# Tah.net
KiCad netlist of a schematic drawn in EAGLE
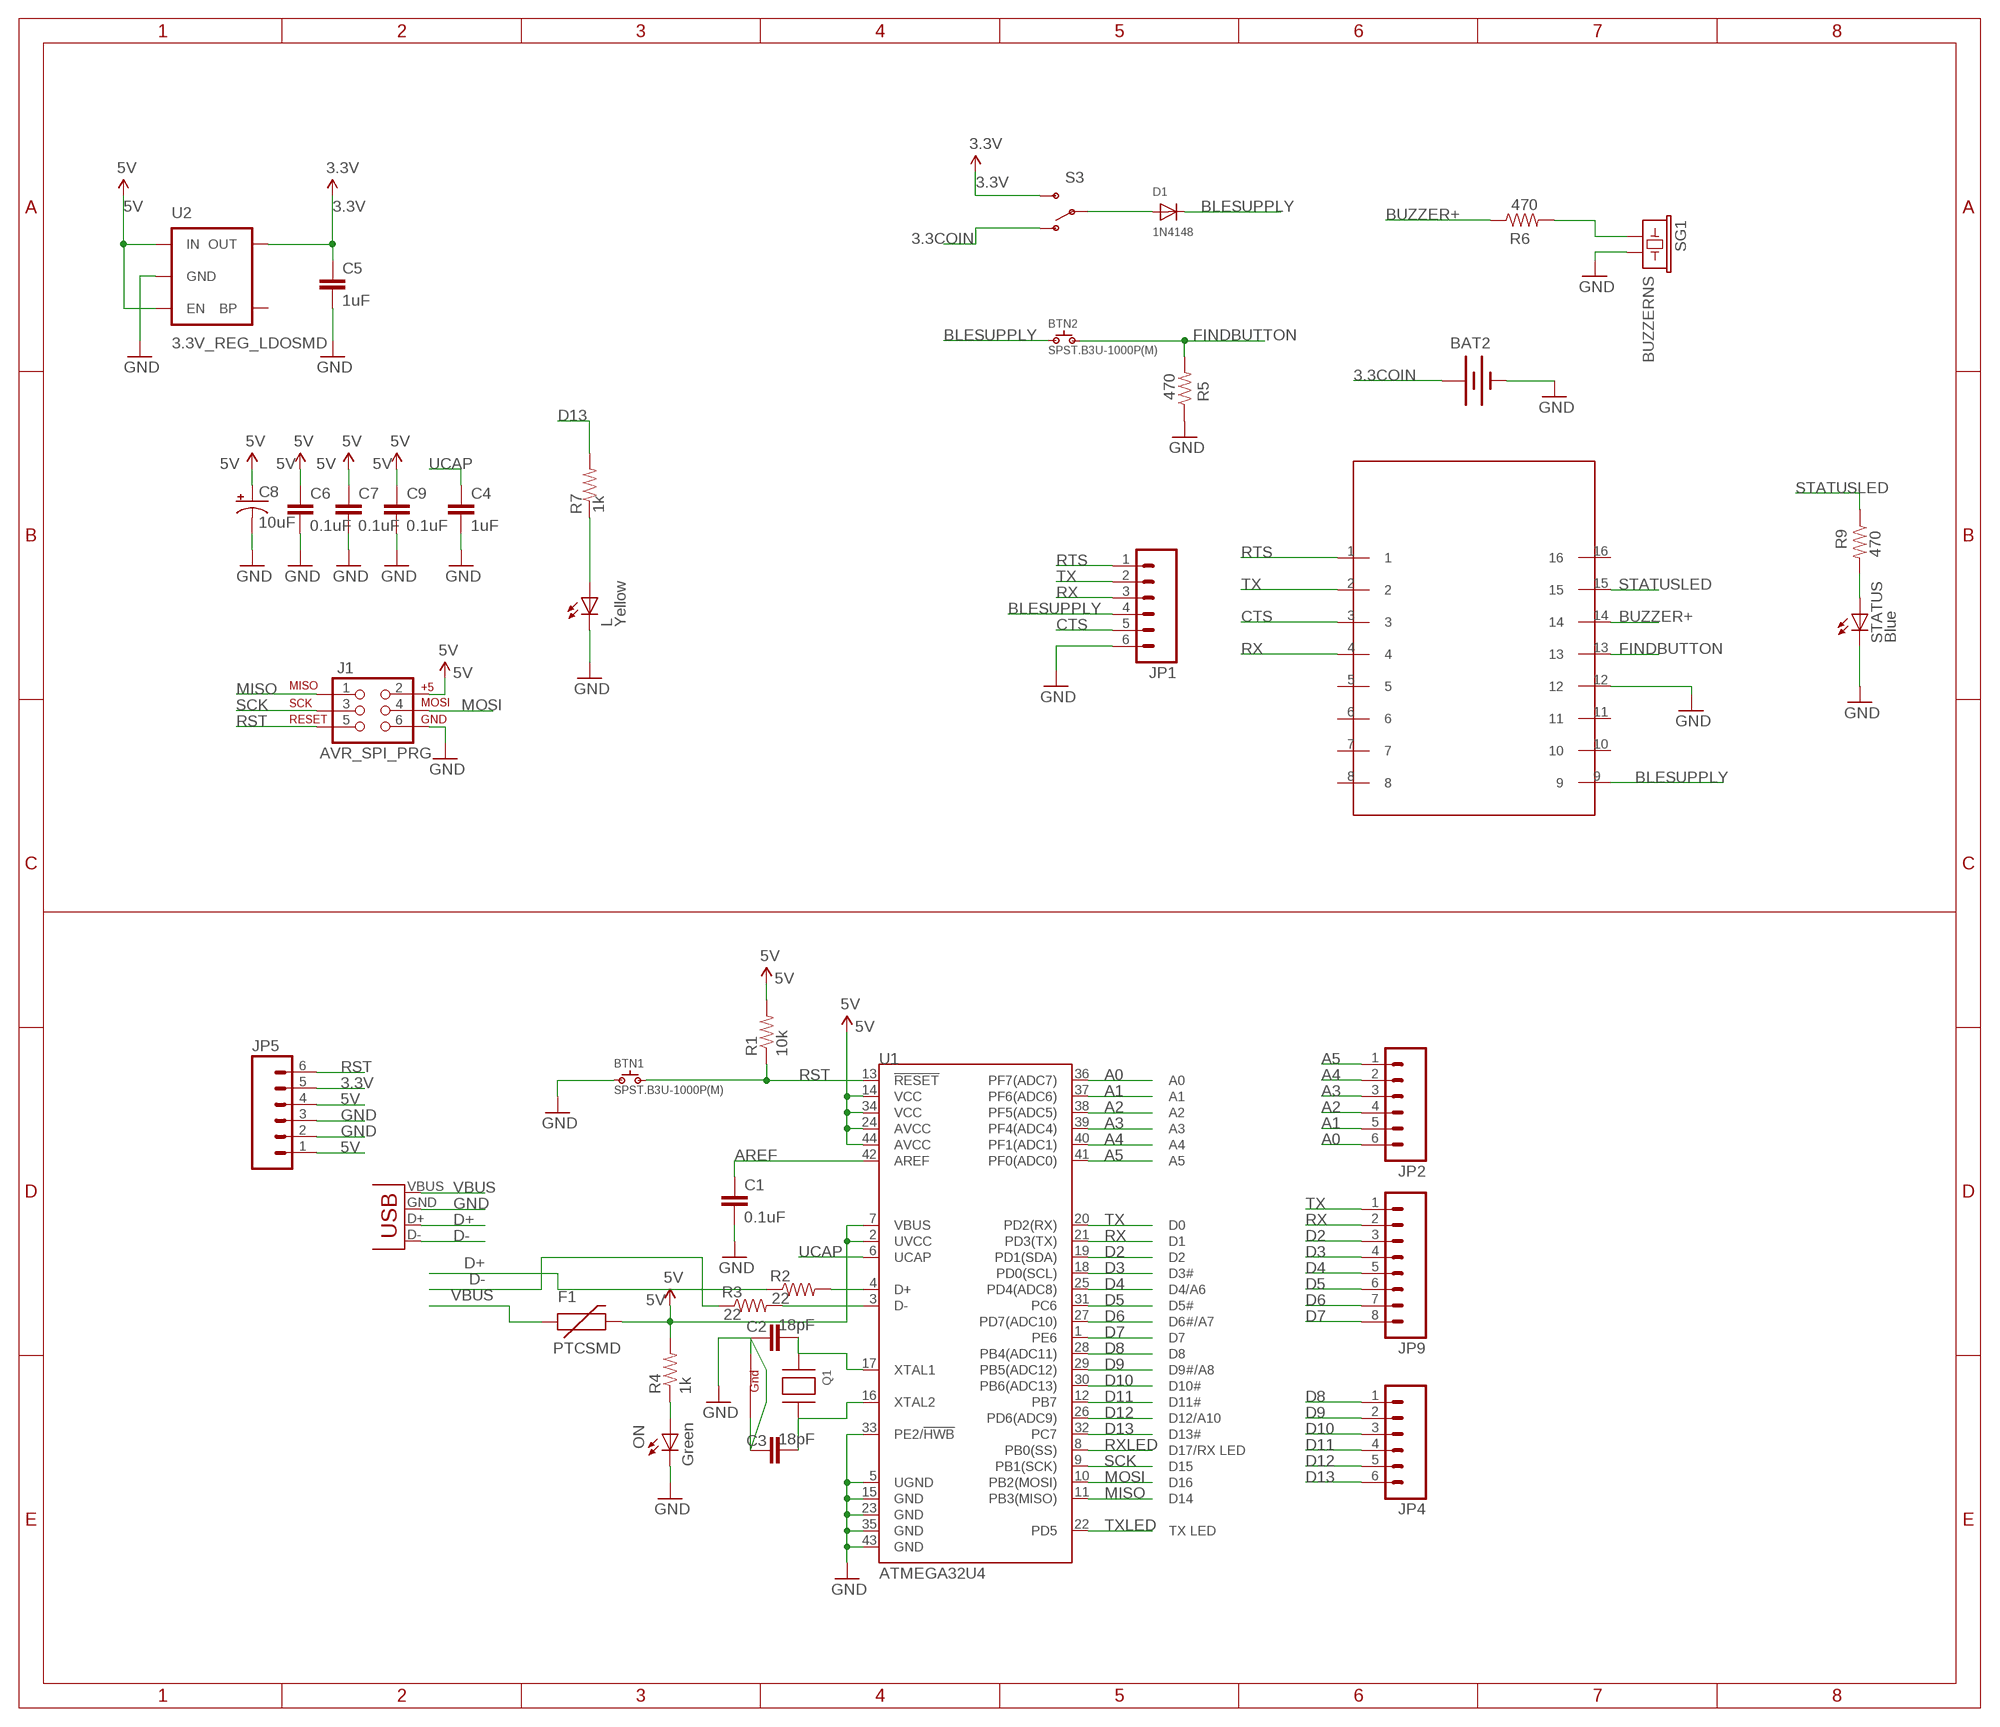
[diagram p0: schematic, sheet 1]

(export (version "E")
  (design (tool "Eeschema 10.0.6"))
  (components
    (comp (ref "BAT2")
      (value "BATTERY20SMD")
      (footprint "eagle-import:BATTCON_20MM")
      (libsource (lib "eagle-import") (part "BATTERY20SMD"))
    )
    (comp (ref "BLE")
      (value "HM-11HM11")
      (footprint "eagle-import:BC05B-SMD")
      (libsource (lib "eagle-import") (part "HM-11HM11"))
    )
    (comp (ref "BTN1")
      (value "SPST.B3U-1000P(M)")
      (footprint "eagle-import:B3U-1000P(M)")
      (libsource (lib "eagle-import") (part "SPST.B3U-1000P(M)"))
    )
    (comp (ref "BTN2")
      (value "SPST.B3U-1000P(M)")
      (footprint "eagle-import:B3U-1000P(M)")
      (libsource (lib "eagle-import") (part "SPST.B3U-1000P(M)"))
    )
    (comp (ref "C1")
      (value "0.1uF")
      (footprint "eagle-import:1206")
      (libsource (lib "eagle-import") (part "2.2UF-CERCAP-10009"))
    )
    (comp (ref "C2")
      (value "18pF")
      (footprint "eagle-import:1206")
      (libsource (lib "eagle-import") (part "2.2UF-CERCAP-10009"))
    )
    (comp (ref "C3")
      (value "18pF")
      (footprint "eagle-import:1206")
      (libsource (lib "eagle-import") (part "2.2UF-CERCAP-10009"))
    )
    (comp (ref "C4")
      (value "1uF")
      (footprint "eagle-import:1206")
      (libsource (lib "eagle-import") (part "2.2UF-CERCAP-10009"))
    )
    (comp (ref "C5")
      (value "1uF")
      (footprint "eagle-import:1206")
      (libsource (lib "eagle-import") (part "2.2UF-CERCAP-10009"))
    )
    (comp (ref "C6")
      (value "0.1uF")
      (footprint "eagle-import:1206")
      (libsource (lib "eagle-import") (part "2.2UF-CERCAP-10009"))
    )
    (comp (ref "C7")
      (value "0.1uF")
      (footprint "eagle-import:1206")
      (libsource (lib "eagle-import") (part "2.2UF-CERCAP-10009"))
    )
    (comp (ref "C8")
      (value "10uF")
      (footprint "eagle-import:EIA3216")
      (libsource (lib "eagle-import") (part "CAP_POL1206"))
    )
    (comp (ref "C9")
      (value "0.1uF")
      (footprint "eagle-import:1206")
      (libsource (lib "eagle-import") (part "2.2UF-CERCAP-10009"))
    )
    (comp (ref "D1")
      (value "1N4148")
      (footprint "eagle-import:SMADIODE")
      (libsource (lib "eagle-import") (part "DIODESMA"))
    )
    (comp (ref "F1")
      (value "PTCSMD")
      (footprint "eagle-import:PTC-1206")
      (libsource (lib "eagle-import") (part "PTCSMD"))
    )
    (comp (ref "J1")
      (value "AVR_SPI_PRG")
      (footprint "eagle-import:2X3")
      (libsource (lib "eagle-import") (part "AVR_SPI_PRG_6PTH"))
    )
    (comp (ref "JP1")
      (value "M06SIP")
      (footprint "eagle-import:1X06")
      (libsource (lib "eagle-import") (part "M06SIP"))
    )
    (comp (ref "JP2")
      (value "M06SIP")
      (footprint "eagle-import:1X06")
      (libsource (lib "eagle-import") (part "M06SIP"))
    )
    (comp (ref "JP4")
      (value "M06SIP")
      (footprint "eagle-import:1X06")
      (libsource (lib "eagle-import") (part "M06SIP"))
    )
    (comp (ref "JP5")
      (value "M06SIP")
      (footprint "eagle-import:1X06")
      (libsource (lib "eagle-import") (part "M06SIP"))
    )
    (comp (ref "JP7")
      (value "USB-A-H")
      (footprint "eagle-import:USB-A-H")
      (libsource (lib "eagle-import") (part "USB-A-H"))
    )
    (comp (ref "JP9")
      (value "M081X08")
      (footprint "eagle-import:1X08")
      (libsource (lib "eagle-import") (part "M081X08"))
    )
    (comp (ref "L")
      (value "Yellow")
      (footprint "eagle-import:1206")
      (libsource (lib "eagle-import") (part "LEDSMT1206"))
    )
    (comp (ref "ON")
      (value "Green")
      (footprint "eagle-import:1206")
      (libsource (lib "eagle-import") (part "LEDSMT1206"))
    )
    (comp (ref "Q1")
      (value "XTAL-4-3225")
      (footprint "eagle-import:NX3225")
      (libsource (lib "eagle-import") (part "XTAL-4-3225"))
    )
    (comp (ref "R1")
      (value "10k")
      (footprint "eagle-import:1206")
      (libsource (lib "eagle-import") (part "RESISTOR1206"))
    )
    (comp (ref "R2")
      (value "22")
      (footprint "eagle-import:1206")
      (libsource (lib "eagle-import") (part "RESISTOR1206"))
    )
    (comp (ref "R3")
      (value "22")
      (footprint "eagle-import:1206")
      (libsource (lib "eagle-import") (part "RESISTOR1206"))
    )
    (comp (ref "R4")
      (value "1k")
      (footprint "eagle-import:1206")
      (libsource (lib "eagle-import") (part "RESISTOR1206"))
    )
    (comp (ref "R5")
      (value "470")
      (footprint "eagle-import:1206")
      (libsource (lib "eagle-import") (part "RESISTOR1206"))
    )
    (comp (ref "R6")
      (value "470")
      (footprint "eagle-import:1206")
      (libsource (lib "eagle-import") (part "RESISTOR1206"))
    )
    (comp (ref "R7")
      (value "1k")
      (footprint "eagle-import:1206")
      (libsource (lib "eagle-import") (part "RESISTOR1206"))
    )
    (comp (ref "R9")
      (value "470")
      (footprint "eagle-import:1206")
      (libsource (lib "eagle-import") (part "RESISTOR1206"))
    )
    (comp (ref "S3")
      (value "SWITCH-SPDT-SMD-A")
      (footprint "eagle-import:SWITCH-SPST-SMD-A")
      (libsource (lib "eagle-import") (part "SWITCH-SPDT-SMD-A"))
    )
    (comp (ref "SG1")
      (value "BUZZERNS")
      (footprint "eagle-import:BUZZER-12MM-NS")
      (libsource (lib "eagle-import") (part "BUZZERNS"))
    )
    (comp (ref "STATUS")
      (value "Blue")
      (footprint "eagle-import:1206")
      (libsource (lib "eagle-import") (part "LEDSMT1206"))
    )
    (comp (ref "U1")
      (value "ATMEGA32U4")
      (footprint "eagle-import:SPARKFUN-DIGITALIC_TQFP44")
      (libsource (lib "eagle-import") (part "ATMEGA32U4TQFP"))
    )
    (comp (ref "U2")
      (value "3.3V_REG_LDOSMD")
      (footprint "eagle-import:SOT23-5")
      (libsource (lib "eagle-import") (part "V_REG_LDOSMD"))
    )
  )
  (nets
    (net (code "1") (name "/3.3COIN") (class "Default")
      (node (ref "BAT2") (pin "1") (pinfunction "+_1") (pintype "power_in"))
      (node (ref "S3") (pin "1") (pinfunction "O_1") (pintype "passive"))
    )
    (net (code "2") (name "/A0") (class "Default")
      (node (ref "JP2") (pin "6") (pinfunction "6_6") (pintype "passive"))
      (node (ref "U1") (pin "36") (pinfunction "PF7(ADC7)_36") (pintype "bidirectional"))
    )
    (net (code "3") (name "/A1") (class "Default")
      (node (ref "JP2") (pin "5") (pinfunction "5_5") (pintype "passive"))
      (node (ref "U1") (pin "37") (pinfunction "PF6(ADC6)_37") (pintype "bidirectional"))
    )
    (net (code "4") (name "/A2") (class "Default")
      (node (ref "JP2") (pin "4") (pinfunction "4_4") (pintype "passive"))
      (node (ref "U1") (pin "38") (pinfunction "PF5(ADC5)_38") (pintype "bidirectional"))
    )
    (net (code "5") (name "/A3") (class "Default")
      (node (ref "JP2") (pin "3") (pinfunction "3_3") (pintype "passive"))
      (node (ref "U1") (pin "39") (pinfunction "PF4(ADC4)_39") (pintype "bidirectional"))
    )
    (net (code "6") (name "/A4") (class "Default")
      (node (ref "JP2") (pin "2") (pinfunction "2_2") (pintype "passive"))
      (node (ref "U1") (pin "40") (pinfunction "PF1(ADC1)_40") (pintype "bidirectional"))
    )
    (net (code "7") (name "/A5") (class "Default")
      (node (ref "JP2") (pin "1") (pinfunction "1_1") (pintype "passive"))
      (node (ref "U1") (pin "41") (pinfunction "PF0(ADC0)_41") (pintype "bidirectional"))
    )
    (net (code "8") (name "/AREF") (class "Default")
      (node (ref "C1") (pin "1") (pinfunction "1_1") (pintype "passive"))
      (node (ref "U1") (pin "42") (pinfunction "AREF_42") (pintype "bidirectional"))
    )
    (net (code "9") (name "/BLESUPPLY") (class "Default")
      (node (ref "BLE") (pin "9") (pinfunction "9_9") (pintype "bidirectional"))
      (node (ref "BTN2") (pin "1") (pinfunction "1_1") (pintype "bidirectional"))
      (node (ref "D1") (pin "C") (pinfunction "C_C") (pintype "passive"))
      (node (ref "JP1") (pin "4") (pinfunction "4_4") (pintype "passive"))
    )
    (net (code "10") (name "/BUZZER+") (class "Default")
      (node (ref "BLE") (pin "14") (pinfunction "14_14") (pintype "bidirectional"))
      (node (ref "R6") (pin "1") (pinfunction "1_1") (pintype "passive"))
    )
    (net (code "11") (name "/CTS") (class "Default")
      (node (ref "BLE") (pin "3") (pinfunction "3_3") (pintype "bidirectional"))
      (node (ref "JP1") (pin "5") (pinfunction "5_5") (pintype "passive"))
    )
    (net (code "12") (name "/D+") (class "Default")
      (node (ref "JP7") (pin "D+") (pinfunction "D-_D+") (pintype "bidirectional"))
      (node (ref "R2") (pin "1") (pinfunction "1_1") (pintype "passive"))
    )
    (net (code "13") (name "/D-") (class "Default")
      (node (ref "JP7") (pin "D-") (pinfunction "D+_D-") (pintype "bidirectional"))
      (node (ref "R3") (pin "1") (pinfunction "1_1") (pintype "passive"))
    )
    (net (code "14") (name "/D2") (class "Default")
      (node (ref "JP9") (pin "3") (pinfunction "3_3") (pintype "passive"))
      (node (ref "U1") (pin "19") (pinfunction "PD1(SDA)_19") (pintype "bidirectional"))
    )
    (net (code "15") (name "/D3") (class "Default")
      (node (ref "JP9") (pin "4") (pinfunction "4_4") (pintype "passive"))
      (node (ref "U1") (pin "18") (pinfunction "PD0(SCL)_18") (pintype "bidirectional"))
    )
    (net (code "16") (name "/D4") (class "Default")
      (node (ref "JP9") (pin "5") (pinfunction "5_5") (pintype "passive"))
      (node (ref "U1") (pin "25") (pinfunction "PD4(ADC8)_25") (pintype "bidirectional"))
    )
    (net (code "17") (name "/D5") (class "Default")
      (node (ref "JP9") (pin "6") (pinfunction "6_6") (pintype "passive"))
      (node (ref "U1") (pin "31") (pinfunction "PC6_31") (pintype "bidirectional"))
    )
    (net (code "18") (name "/D6") (class "Default")
      (node (ref "JP9") (pin "7") (pinfunction "7_7") (pintype "passive"))
      (node (ref "U1") (pin "27") (pinfunction "PD7(ADC10)_27") (pintype "bidirectional"))
    )
    (net (code "19") (name "/D7") (class "Default")
      (node (ref "JP9") (pin "8") (pinfunction "8_8") (pintype "passive"))
      (node (ref "U1") (pin "1") (pinfunction "PE6_1") (pintype "bidirectional"))
    )
    (net (code "20") (name "/D8") (class "Default")
      (node (ref "JP4") (pin "1") (pinfunction "1_1") (pintype "passive"))
      (node (ref "U1") (pin "28") (pinfunction "PB4(ADC11)_28") (pintype "bidirectional"))
    )
    (net (code "21") (name "/D9") (class "Default")
      (node (ref "JP4") (pin "2") (pinfunction "2_2") (pintype "passive"))
      (node (ref "U1") (pin "29") (pinfunction "PB5(ADC12)_29") (pintype "bidirectional"))
    )
    (net (code "22") (name "/D10") (class "Default")
      (node (ref "JP4") (pin "3") (pinfunction "3_3") (pintype "passive"))
      (node (ref "U1") (pin "30") (pinfunction "PB6(ADC13)_30") (pintype "bidirectional"))
    )
    (net (code "23") (name "/D11") (class "Default")
      (node (ref "JP4") (pin "4") (pinfunction "4_4") (pintype "passive"))
      (node (ref "U1") (pin "12") (pinfunction "PB7_12") (pintype "bidirectional"))
    )
    (net (code "24") (name "/D12") (class "Default")
      (node (ref "JP4") (pin "5") (pinfunction "5_5") (pintype "passive"))
      (node (ref "U1") (pin "26") (pinfunction "PD6(ADC9)_26") (pintype "bidirectional"))
    )
    (net (code "25") (name "/D13") (class "Default")
      (node (ref "JP4") (pin "6") (pinfunction "6_6") (pintype "passive"))
      (node (ref "R7") (pin "2") (pinfunction "2_2") (pintype "passive"))
      (node (ref "U1") (pin "32") (pinfunction "PC7_32") (pintype "bidirectional"))
    )
    (net (code "26") (name "/FINDBUTTON") (class "Default")
      (node (ref "BLE") (pin "13") (pinfunction "13_13") (pintype "bidirectional"))
      (node (ref "BTN2") (pin "2") (pinfunction "2_2") (pintype "bidirectional"))
      (node (ref "R5") (pin "2") (pinfunction "2_2") (pintype "passive"))
    )
    (net (code "27") (name "/MISO") (class "Default")
      (node (ref "J1") (pin "1") (pinfunction "1_1") (pintype "passive"))
      (node (ref "U1") (pin "11") (pinfunction "PB3(MISO)_11") (pintype "bidirectional"))
    )
    (net (code "28") (name "/MOSI") (class "Default")
      (node (ref "J1") (pin "4") (pinfunction "4_4") (pintype "passive"))
      (node (ref "U1") (pin "10") (pinfunction "PB2(MOSI)_10") (pintype "bidirectional"))
    )
    (net (code "29") (name "/RST") (class "Default")
      (node (ref "BTN1") (pin "2") (pinfunction "2_2") (pintype "bidirectional"))
      (node (ref "J1") (pin "5") (pinfunction "5_5") (pintype "passive"))
      (node (ref "JP5") (pin "6") (pinfunction "6_6") (pintype "passive"))
      (node (ref "R1") (pin "1") (pinfunction "1_1") (pintype "passive"))
      (node (ref "U1") (pin "13") (pinfunction "~{RESET}_13") (pintype "bidirectional"))
    )
    (net (code "30") (name "/RTS") (class "Default")
      (node (ref "BLE") (pin "1") (pinfunction "1_1") (pintype "bidirectional"))
      (node (ref "JP1") (pin "1") (pinfunction "1_1") (pintype "passive"))
    )
    (net (code "31") (name "/RX") (class "Default")
      (node (ref "BLE") (pin "4") (pinfunction "4_4") (pintype "bidirectional"))
      (node (ref "JP1") (pin "3") (pinfunction "3_3") (pintype "passive"))
      (node (ref "JP9") (pin "2") (pinfunction "2_2") (pintype "passive"))
      (node (ref "U1") (pin "21") (pinfunction "PD3(TX)_21") (pintype "bidirectional"))
    )
    (net (code "32") (name "/RXLED") (class "Default")
      (node (ref "U1") (pin "8") (pinfunction "PB0(SS)_8") (pintype "bidirectional"))
    )
    (net (code "33") (name "/SCK") (class "Default")
      (node (ref "J1") (pin "3") (pinfunction "3_3") (pintype "passive"))
      (node (ref "U1") (pin "9") (pinfunction "PB1(SCK)_9") (pintype "bidirectional"))
    )
    (net (code "34") (name "/STATUSLED") (class "Default")
      (node (ref "BLE") (pin "15") (pinfunction "15_15") (pintype "bidirectional"))
      (node (ref "R9") (pin "1") (pinfunction "1_1") (pintype "passive"))
    )
    (net (code "35") (name "/TX") (class "Default")
      (node (ref "BLE") (pin "2") (pinfunction "2_2") (pintype "bidirectional"))
      (node (ref "JP1") (pin "2") (pinfunction "2_2") (pintype "passive"))
      (node (ref "JP9") (pin "1") (pinfunction "1_1") (pintype "passive"))
      (node (ref "U1") (pin "20") (pinfunction "PD2(RX)_20") (pintype "bidirectional"))
    )
    (net (code "36") (name "/TXLED") (class "Default")
      (node (ref "U1") (pin "22") (pinfunction "PD5_22") (pintype "bidirectional"))
    )
    (net (code "37") (name "/UCAP") (class "Default")
      (node (ref "C4") (pin "1") (pinfunction "1_1") (pintype "passive"))
      (node (ref "U1") (pin "6") (pinfunction "UCAP_6") (pintype "bidirectional"))
    )
    (net (code "38") (name "/VBUS") (class "Default")
      (node (ref "F1") (pin "1") (pinfunction "1_1") (pintype "bidirectional"))
      (node (ref "JP7") (pin "VBUS") (pinfunction "GND_VBUS") (pintype "bidirectional"))
    )
    (net (code "39") (name "3.3V") (class "Default")
      (node (ref "C5") (pin "1") (pinfunction "1_1") (pintype "passive"))
      (node (ref "JP5") (pin "5") (pinfunction "5_5") (pintype "passive"))
      (node (ref "S3") (pin "3") (pinfunction "S_3") (pintype "passive"))
      (node (ref "U2") (pin "5") (pinfunction "OUT_5") (pintype "passive"))
    )
    (net (code "40") (name "5V") (class "Default")
      (node (ref "C6") (pin "1") (pinfunction "1_1") (pintype "passive"))
      (node (ref "C7") (pin "1") (pinfunction "1_1") (pintype "passive"))
      (node (ref "C8") (pin "A") (pinfunction "+_A") (pintype "passive"))
      (node (ref "C9") (pin "1") (pinfunction "1_1") (pintype "passive"))
      (node (ref "F1") (pin "2") (pinfunction "2_2") (pintype "bidirectional"))
      (node (ref "J1") (pin "2") (pinfunction "2_2") (pintype "passive"))
      (node (ref "JP5") (pin "1") (pinfunction "1_1") (pintype "passive"))
      (node (ref "JP5") (pin "4") (pinfunction "4_4") (pintype "passive"))
      (node (ref "R1") (pin "2") (pinfunction "2_2") (pintype "passive"))
      (node (ref "R4") (pin "2") (pinfunction "2_2") (pintype "passive"))
      (node (ref "U1") (pin "14") (pinfunction "VCC_14") (pintype "bidirectional"))
      (node (ref "U1") (pin "2") (pinfunction "UVCC_2") (pintype "bidirectional"))
      (node (ref "U1") (pin "24") (pinfunction "AVCC_24") (pintype "bidirectional"))
      (node (ref "U1") (pin "34") (pinfunction "VCC_34") (pintype "bidirectional"))
      (node (ref "U1") (pin "44") (pinfunction "AVCC_44") (pintype "bidirectional"))
      (node (ref "U1") (pin "7") (pinfunction "VBUS_7") (pintype "bidirectional"))
      (node (ref "U2") (pin "1") (pinfunction "IN_1") (pintype "input"))
      (node (ref "U2") (pin "3") (pinfunction "EN_3") (pintype "input"))
    )
    (net (code "41") (name "GND") (class "Default")
      (node (ref "BAT2") (pin "2") (pinfunction "-_2") (pintype "power_in"))
      (node (ref "BLE") (pin "12") (pinfunction "12_12") (pintype "bidirectional"))
      (node (ref "BTN1") (pin "1") (pinfunction "1_1") (pintype "bidirectional"))
      (node (ref "C1") (pin "2") (pinfunction "2_2") (pintype "passive"))
      (node (ref "C2") (pin "1") (pinfunction "1_1") (pintype "passive"))
      (node (ref "C3") (pin "1") (pinfunction "1_1") (pintype "passive"))
      (node (ref "C4") (pin "2") (pinfunction "2_2") (pintype "passive"))
      (node (ref "C5") (pin "2") (pinfunction "2_2") (pintype "passive"))
      (node (ref "C6") (pin "2") (pinfunction "2_2") (pintype "passive"))
      (node (ref "C7") (pin "2") (pinfunction "2_2") (pintype "passive"))
      (node (ref "C8") (pin "C") (pinfunction "-_C") (pintype "passive"))
      (node (ref "C9") (pin "2") (pinfunction "2_2") (pintype "passive"))
      (node (ref "J1") (pin "6") (pinfunction "6_6") (pintype "passive"))
      (node (ref "JP1") (pin "6") (pinfunction "6_6") (pintype "passive"))
      (node (ref "JP5") (pin "2") (pinfunction "2_2") (pintype "passive"))
      (node (ref "JP5") (pin "3") (pinfunction "3_3") (pintype "passive"))
      (node (ref "JP7") (pin "GND") (pinfunction "VBUS_GND") (pintype "bidirectional"))
      (node (ref "L") (pin "C") (pinfunction "C_C") (pintype "passive"))
      (node (ref "ON") (pin "C") (pinfunction "C_C") (pintype "passive"))
      (node (ref "Q1") (pin "2") (pinfunction "G2_2") (pintype "power_in"))
      (node (ref "Q1") (pin "4") (pinfunction "G1_4") (pintype "power_in"))
      (node (ref "R5") (pin "1") (pinfunction "1_1") (pintype "passive"))
      (node (ref "SG1") (pin "-") (pinfunction "2_-") (pintype "passive"))
      (node (ref "STATUS") (pin "C") (pinfunction "C_C") (pintype "passive"))
      (node (ref "U1") (pin "15") (pinfunction "GND_15") (pintype "bidirectional"))
      (node (ref "U1") (pin "23") (pinfunction "GND_23") (pintype "bidirectional"))
      (node (ref "U1") (pin "33") (pinfunction "PE2/~{HWB}_33") (pintype "bidirectional"))
      (node (ref "U1") (pin "35") (pinfunction "GND_35") (pintype "bidirectional"))
      (node (ref "U1") (pin "43") (pinfunction "GND_43") (pintype "bidirectional"))
      (node (ref "U1") (pin "5") (pinfunction "UGND_5") (pintype "bidirectional"))
      (node (ref "U2") (pin "2") (pinfunction "GND_2") (pintype "input"))
    )
    (net (code "42") (name "Net-(L-PadA)") (class "Default")
      (node (ref "L") (pin "A") (pinfunction "A_A") (pintype "passive"))
      (node (ref "R7") (pin "1") (pinfunction "1_1") (pintype "passive"))
    )
    (net (code "43") (name "Net-(ON-PadA)") (class "Default")
      (node (ref "ON") (pin "A") (pinfunction "A_A") (pintype "passive"))
      (node (ref "R4") (pin "1") (pinfunction "1_1") (pintype "passive"))
    )
    (net (code "44") (name "Net-(Q1-X1)") (class "Default")
      (node (ref "C2") (pin "2") (pinfunction "2_2") (pintype "passive"))
      (node (ref "Q1") (pin "1") (pinfunction "X1_1") (pintype "bidirectional"))
      (node (ref "U1") (pin "17") (pinfunction "XTAL1_17") (pintype "bidirectional"))
    )
    (net (code "45") (name "Net-(Q1-X2)") (class "Default")
      (node (ref "C3") (pin "2") (pinfunction "2_2") (pintype "passive"))
      (node (ref "Q1") (pin "3") (pinfunction "X2_3") (pintype "bidirectional"))
      (node (ref "U1") (pin "16") (pinfunction "XTAL2_16") (pintype "bidirectional"))
    )
    (net (code "46") (name "Net-(R9-Pad2)") (class "Default")
      (node (ref "R9") (pin "2") (pinfunction "2_2") (pintype "passive"))
      (node (ref "STATUS") (pin "A") (pinfunction "A_A") (pintype "passive"))
    )
    (net (code "47") (name "Net-(S3-P)") (class "Default")
      (node (ref "D1") (pin "A") (pinfunction "A_A") (pintype "passive"))
      (node (ref "S3") (pin "2") (pinfunction "P_2") (pintype "passive"))
    )
    (net (code "48") (name "Net-(SG1-1)") (class "Default")
      (node (ref "R6") (pin "2") (pinfunction "2_2") (pintype "passive"))
      (node (ref "SG1") (pin "+") (pinfunction "1_+") (pintype "passive"))
    )
    (net (code "49") (name "Net-(U1-D+)") (class "Default")
      (node (ref "R2") (pin "2") (pinfunction "2_2") (pintype "passive"))
      (node (ref "U1") (pin "4") (pinfunction "D+_4") (pintype "bidirectional"))
    )
    (net (code "50") (name "Net-(U1-D-)") (class "Default")
      (node (ref "R3") (pin "2") (pinfunction "2_2") (pintype "passive"))
      (node (ref "U1") (pin "3") (pinfunction "D-_3") (pintype "bidirectional"))
    )
    (net (code "51") (name "unconnected-(BLE-Pad5)") (class "Default")
      (node (ref "BLE") (pin "5") (pinfunction "5_5") (pintype "bidirectional"))
    )
    (net (code "52") (name "unconnected-(BLE-Pad6)") (class "Default")
      (node (ref "BLE") (pin "6") (pinfunction "6_6") (pintype "bidirectional"))
    )
    (net (code "53") (name "unconnected-(BLE-Pad7)") (class "Default")
      (node (ref "BLE") (pin "7") (pinfunction "7_7") (pintype "bidirectional"))
    )
    (net (code "54") (name "unconnected-(BLE-Pad8)") (class "Default")
      (node (ref "BLE") (pin "8") (pinfunction "8_8") (pintype "bidirectional"))
    )
    (net (code "55") (name "unconnected-(BLE-Pad10)") (class "Default")
      (node (ref "BLE") (pin "10") (pinfunction "10_10") (pintype "bidirectional"))
    )
    (net (code "56") (name "unconnected-(BLE-Pad11)") (class "Default")
      (node (ref "BLE") (pin "11") (pinfunction "11_11") (pintype "bidirectional"))
    )
    (net (code "57") (name "unconnected-(BLE-Pad16)") (class "Default")
      (node (ref "BLE") (pin "16") (pinfunction "16_16") (pintype "bidirectional"))
    )
    (net (code "58") (name "unconnected-(U2-BP-Pad4)") (class "Default")
      (node (ref "U2") (pin "4") (pinfunction "BP_4") (pintype "input"))
    )
  )
)
